# NeoCoreShield2.net
KiCad netlist of a schematic drawn in EAGLE
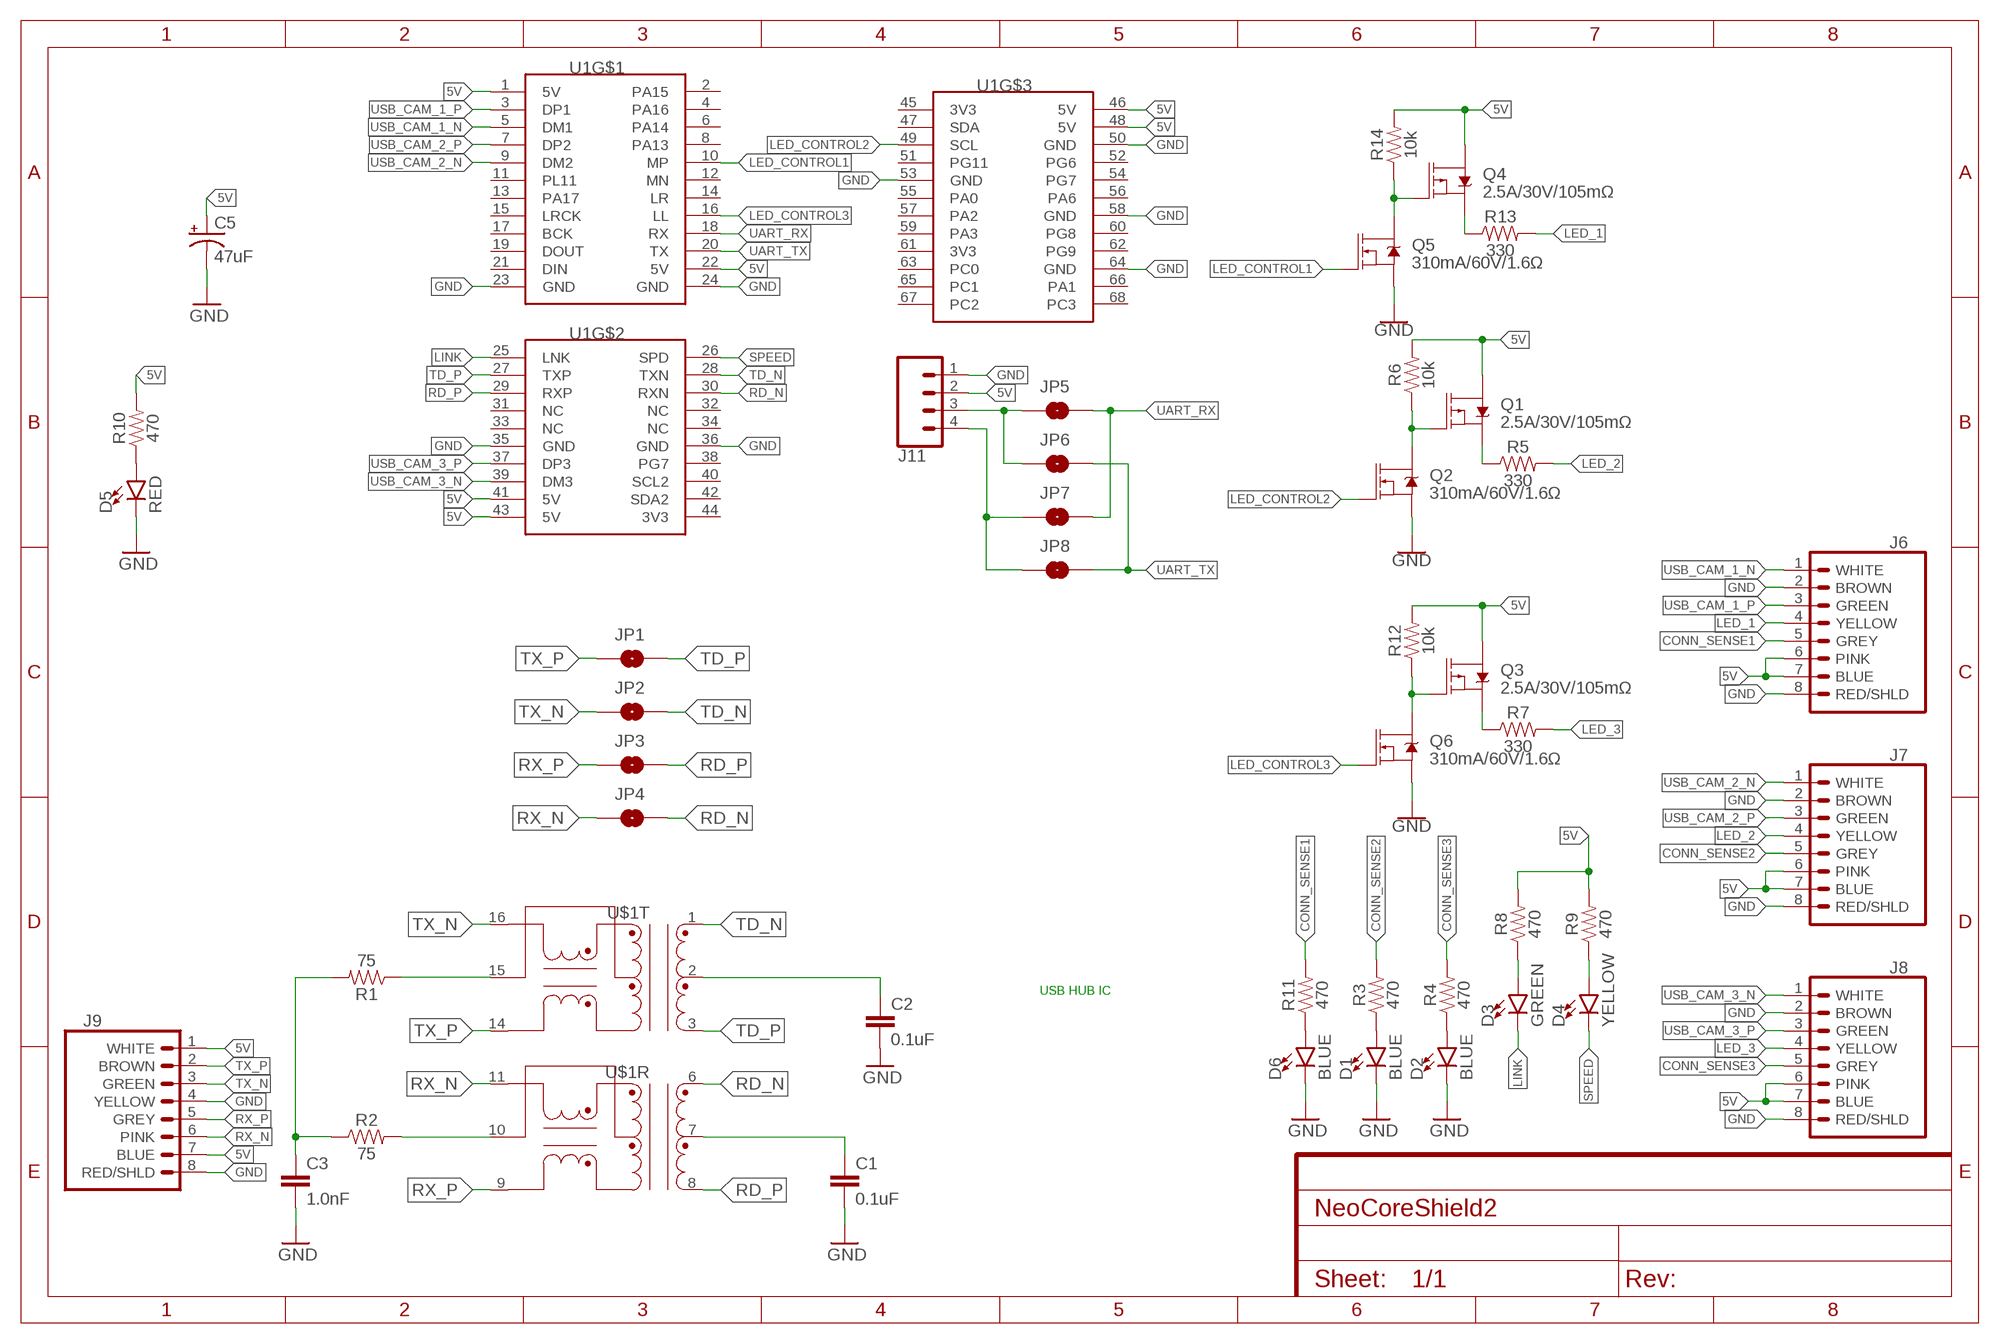
[diagram p0: schematic, sheet 1]

(export (version "E")
  (design (tool "Eeschema 10.0.6"))
  (components
    (comp (ref "C1")
      (value "0.1uF")
      (footprint "eagle-import:0603")
      (libsource (lib "eagle-import") (part "0.1UF-0603-25V-(+80/-20%)"))
    )
    (comp (ref "C2")
      (value "0.1uF")
      (footprint "eagle-import:0603")
      (libsource (lib "eagle-import") (part "0.1UF-0603-25V-(+80/-20%)"))
    )
    (comp (ref "C3")
      (value "1.0nF")
      (footprint "eagle-import:1206")
      (libsource (lib "eagle-import") (part "1.0UF-1206-50V-10%"))
    )
    (comp (ref "C5")
      (value "47uF")
      (footprint "eagle-import:PANASONIC_D")
      (libsource (lib "eagle-import") (part "47UF-POLAR-PANASONIC_D-35V-20%"))
    )
    (comp (ref "D1")
      (value "BLUE")
      (footprint "eagle-import:0805")
      (libsource (lib "eagle-import") (part "LED-0805"))
    )
    (comp (ref "D2")
      (value "BLUE")
      (footprint "eagle-import:0805")
      (libsource (lib "eagle-import") (part "LED-0805"))
    )
    (comp (ref "D3")
      (value "GREEN")
      (footprint "eagle-import:0805")
      (libsource (lib "eagle-import") (part "LED-0805"))
    )
    (comp (ref "D4")
      (value "YELLOW")
      (footprint "eagle-import:0805")
      (libsource (lib "eagle-import") (part "LED-0805"))
    )
    (comp (ref "D5")
      (value "RED")
      (footprint "eagle-import:0805")
      (libsource (lib "eagle-import") (part "LED-0805"))
    )
    (comp (ref "D6")
      (value "BLUE")
      (footprint "eagle-import:0805")
      (libsource (lib "eagle-import") (part "LED-0805"))
    )
    (comp (ref "J6")
      (value "BINDER_M12_PAR_8_DIP")
      (footprint "eagle-import:BINDER_M12_PAR_8_DIP")
      (libsource (lib "eagle-import") (part "BINDER_M12_PAR_8_DIP"))
    )
    (comp (ref "J7")
      (value "BINDER_M12_PAR_8_DIP")
      (footprint "eagle-import:BINDER_M12_PAR_8_DIP")
      (libsource (lib "eagle-import") (part "BINDER_M12_PAR_8_DIP"))
    )
    (comp (ref "J8")
      (value "BINDER_M12_PAR_8_DIP")
      (footprint "eagle-import:BINDER_M12_PAR_8_DIP")
      (libsource (lib "eagle-import") (part "BINDER_M12_PAR_8_DIP"))
    )
    (comp (ref "J9")
      (value "BINDER_M12_PAR_8_DIP")
      (footprint "eagle-import:BINDER_M12_PAR_8_DIP")
      (libsource (lib "eagle-import") (part "BINDER_M12_PAR_8_DIP"))
    )
    (comp (ref "J11")
      (value "CONN_04")
      (footprint "eagle-import:1X04")
      (libsource (lib "eagle-import") (part "CONN_04"))
    )
    (comp (ref "JP1")
      (value "JUMPER-SMT_2_NO_SILK")
      (footprint "eagle-import:SMT-JUMPER_2_NO_SILK")
      (libsource (lib "eagle-import") (part "JUMPER-SMT_2_NO_SILK"))
    )
    (comp (ref "JP2")
      (value "JUMPER-SMT_2_NO_SILK")
      (footprint "eagle-import:SMT-JUMPER_2_NO_SILK")
      (libsource (lib "eagle-import") (part "JUMPER-SMT_2_NO_SILK"))
    )
    (comp (ref "JP3")
      (value "JUMPER-SMT_2_NO_SILK")
      (footprint "eagle-import:SMT-JUMPER_2_NO_SILK")
      (libsource (lib "eagle-import") (part "JUMPER-SMT_2_NO_SILK"))
    )
    (comp (ref "JP4")
      (value "JUMPER-SMT_2_NO_SILK")
      (footprint "eagle-import:SMT-JUMPER_2_NO_SILK")
      (libsource (lib "eagle-import") (part "JUMPER-SMT_2_NO_SILK"))
    )
    (comp (ref "JP5")
      (value "JUMPER-SMT_2_NO_SILK")
      (footprint "eagle-import:SMT-JUMPER_2_NO_SILK")
      (libsource (lib "eagle-import") (part "JUMPER-SMT_2_NO_SILK"))
    )
    (comp (ref "JP6")
      (value "JUMPER-SMT_2_NO_SILK")
      (footprint "eagle-import:SMT-JUMPER_2_NO_SILK")
      (libsource (lib "eagle-import") (part "JUMPER-SMT_2_NO_SILK"))
    )
    (comp (ref "JP7")
      (value "JUMPER-SMT_2_NO_SILK")
      (footprint "eagle-import:SMT-JUMPER_2_NO_SILK")
      (libsource (lib "eagle-import") (part "JUMPER-SMT_2_NO_SILK"))
    )
    (comp (ref "JP8")
      (value "JUMPER-SMT_2_NO_SILK")
      (footprint "eagle-import:SMT-JUMPER_2_NO_SILK")
      (libsource (lib "eagle-import") (part "JUMPER-SMT_2_NO_SILK"))
    )
    (comp (ref "Q1")
      (value "2.5A/30V/105mΩ")
      (footprint "eagle-import:SOT23-3")
      (libsource (lib "eagle-import") (part "MOSFET_PCH-DMG2307L"))
    )
    (comp (ref "Q2")
      (value "310mA/60V/1.6Ω")
      (footprint "eagle-import:SOT323")
      (libsource (lib "eagle-import") (part "MOSFET-NCH-2N7002PW"))
    )
    (comp (ref "Q3")
      (value "2.5A/30V/105mΩ")
      (footprint "eagle-import:SOT23-3")
      (libsource (lib "eagle-import") (part "MOSFET_PCH-DMG2307L"))
    )
    (comp (ref "Q4")
      (value "2.5A/30V/105mΩ")
      (footprint "eagle-import:SOT23-3")
      (libsource (lib "eagle-import") (part "MOSFET_PCH-DMG2307L"))
    )
    (comp (ref "Q5")
      (value "310mA/60V/1.6Ω")
      (footprint "eagle-import:SOT323")
      (libsource (lib "eagle-import") (part "MOSFET-NCH-2N7002PW"))
    )
    (comp (ref "Q6")
      (value "310mA/60V/1.6Ω")
      (footprint "eagle-import:SOT323")
      (libsource (lib "eagle-import") (part "MOSFET-NCH-2N7002PW"))
    )
    (comp (ref "R1")
      (value "75")
      (footprint "eagle-import:0603")
      (libsource (lib "eagle-import") (part "75KOHM-0603-1/10W-1%"))
    )
    (comp (ref "R2")
      (value "75")
      (footprint "eagle-import:0603")
      (libsource (lib "eagle-import") (part "75KOHM-0603-1/10W-1%"))
    )
    (comp (ref "R3")
      (value "470")
      (footprint "eagle-import:0603")
      (libsource (lib "eagle-import") (part "0OHM-0603-1/10W-5%"))
    )
    (comp (ref "R4")
      (value "470")
      (footprint "eagle-import:0603")
      (libsource (lib "eagle-import") (part "0OHM-0603-1/10W-5%"))
    )
    (comp (ref "R5")
      (value "330")
      (footprint "eagle-import:0805")
      (libsource (lib "eagle-import") (part "RESISTOR0805"))
    )
    (comp (ref "R6")
      (value "10k")
      (footprint "eagle-import:0603")
      (libsource (lib "eagle-import") (part "10KOHM-0603-1/10W-1%"))
    )
    (comp (ref "R7")
      (value "330")
      (footprint "eagle-import:0805")
      (libsource (lib "eagle-import") (part "RESISTOR0805"))
    )
    (comp (ref "R8")
      (value "470")
      (footprint "eagle-import:0603")
      (libsource (lib "eagle-import") (part "0OHM-0603-1/10W-5%"))
    )
    (comp (ref "R9")
      (value "470")
      (footprint "eagle-import:0603")
      (libsource (lib "eagle-import") (part "0OHM-0603-1/10W-5%"))
    )
    (comp (ref "R10")
      (value "470")
      (footprint "eagle-import:0603")
      (libsource (lib "eagle-import") (part "0OHM-0603-1/10W-5%"))
    )
    (comp (ref "R11")
      (value "470")
      (footprint "eagle-import:0603")
      (libsource (lib "eagle-import") (part "0OHM-0603-1/10W-5%"))
    )
    (comp (ref "R12")
      (value "10k")
      (footprint "eagle-import:0603")
      (libsource (lib "eagle-import") (part "10KOHM-0603-1/10W-1%"))
    )
    (comp (ref "R13")
      (value "330")
      (footprint "eagle-import:0805")
      (libsource (lib "eagle-import") (part "RESISTOR0805"))
    )
    (comp (ref "R14")
      (value "10k")
      (footprint "eagle-import:0603")
      (libsource (lib "eagle-import") (part "10KOHM-0603-1/10W-1%"))
    )
    (comp (ref "U$1")
      (value "ETH-TRANS")
      (footprint "eagle-import:SOIC-16-WIDE")
      (libsource (lib "eagle-import") (part "ETH-TRANS"))
    )
    (comp (ref "U1")
      (value "NANO_PI_NEO_CORE")
      (footprint "eagle-import:NANO_PI_NEO_CORE")
      (libsource (lib "eagle-import") (part "NANO_PI_NEO_CORE"))
    )
  )
  (nets
    (net (code "1") (name "5V") (class "Default")
      (node (ref "C5") (pin "+") (pinfunction "+_+") (pintype "passive"))
      (node (ref "J11") (pin "2") (pinfunction "2_2") (pintype "passive"))
      (node (ref "J6") (pin "6") (pinfunction "PINK_6") (pintype "passive"))
      (node (ref "J6") (pin "7") (pinfunction "BLUE_7") (pintype "passive"))
      (node (ref "J7") (pin "6") (pinfunction "PINK_6") (pintype "passive"))
      (node (ref "J7") (pin "7") (pinfunction "BLUE_7") (pintype "passive"))
      (node (ref "J8") (pin "6") (pinfunction "PINK_6") (pintype "passive"))
      (node (ref "J8") (pin "7") (pinfunction "BLUE_7") (pintype "passive"))
      (node (ref "J9") (pin "1") (pinfunction "WHITE_1") (pintype "passive"))
      (node (ref "J9") (pin "7") (pinfunction "BLUE_7") (pintype "passive"))
      (node (ref "Q1") (pin "3") (pinfunction "D_3") (pintype "bidirectional"))
      (node (ref "Q3") (pin "3") (pinfunction "D_3") (pintype "bidirectional"))
      (node (ref "Q4") (pin "3") (pinfunction "D_3") (pintype "bidirectional"))
      (node (ref "R10") (pin "2") (pinfunction "2_2") (pintype "passive"))
      (node (ref "R12") (pin "2") (pinfunction "2_2") (pintype "passive"))
      (node (ref "R14") (pin "2") (pinfunction "2_2") (pintype "passive"))
      (node (ref "R6") (pin "2") (pinfunction "2_2") (pintype "passive"))
      (node (ref "R8") (pin "2") (pinfunction "2_2") (pintype "passive"))
      (node (ref "R9") (pin "2") (pinfunction "2_2") (pintype "passive"))
      (node (ref "U1") (pin "1") (pinfunction "5V_1") (pintype "bidirectional"))
      (node (ref "U1") (pin "22") (pinfunction "5V_22") (pintype "bidirectional"))
      (node (ref "U1") (pin "41") (pinfunction "5V_41") (pintype "bidirectional"))
      (node (ref "U1") (pin "43") (pinfunction "5V_43") (pintype "bidirectional"))
      (node (ref "U1") (pin "46") (pinfunction "5V_46") (pintype "bidirectional"))
      (node (ref "U1") (pin "48") (pinfunction "5V_48") (pintype "bidirectional"))
    )
    (net (code "2") (name "CONN_SENSE1") (class "Default")
      (node (ref "J6") (pin "5") (pinfunction "GREY_5") (pintype "passive"))
      (node (ref "R11") (pin "2") (pinfunction "2_2") (pintype "passive"))
    )
    (net (code "3") (name "CONN_SENSE2") (class "Default")
      (node (ref "J7") (pin "5") (pinfunction "GREY_5") (pintype "passive"))
      (node (ref "R3") (pin "2") (pinfunction "2_2") (pintype "passive"))
    )
    (net (code "4") (name "CONN_SENSE3") (class "Default")
      (node (ref "J8") (pin "5") (pinfunction "GREY_5") (pintype "passive"))
      (node (ref "R4") (pin "2") (pinfunction "2_2") (pintype "passive"))
    )
    (net (code "5") (name "GND") (class "Default")
      (node (ref "C1") (pin "2") (pinfunction "2_2") (pintype "passive"))
      (node (ref "C2") (pin "2") (pinfunction "2_2") (pintype "passive"))
      (node (ref "C3") (pin "2") (pinfunction "2_2") (pintype "passive"))
      (node (ref "C5") (pin "-") (pinfunction "-_-") (pintype "passive"))
      (node (ref "D1") (pin "C") (pinfunction "C_C") (pintype "passive"))
      (node (ref "D2") (pin "C") (pinfunction "C_C") (pintype "passive"))
      (node (ref "D5") (pin "C") (pinfunction "C_C") (pintype "passive"))
      (node (ref "D6") (pin "C") (pinfunction "C_C") (pintype "passive"))
      (node (ref "J11") (pin "1") (pinfunction "1_1") (pintype "passive"))
      (node (ref "J6") (pin "2") (pinfunction "BROWN_2") (pintype "passive"))
      (node (ref "J6") (pin "8") (pinfunction "RED/SHLD_8") (pintype "passive"))
      (node (ref "J7") (pin "2") (pinfunction "BROWN_2") (pintype "passive"))
      (node (ref "J7") (pin "8") (pinfunction "RED/SHLD_8") (pintype "passive"))
      (node (ref "J8") (pin "2") (pinfunction "BROWN_2") (pintype "passive"))
      (node (ref "J8") (pin "8") (pinfunction "RED/SHLD_8") (pintype "passive"))
      (node (ref "J9") (pin "4") (pinfunction "YELLOW_4") (pintype "passive"))
      (node (ref "J9") (pin "8") (pinfunction "RED/SHLD_8") (pintype "passive"))
      (node (ref "Q2") (pin "2") (pinfunction "S_2") (pintype "bidirectional"))
      (node (ref "Q5") (pin "2") (pinfunction "S_2") (pintype "bidirectional"))
      (node (ref "Q6") (pin "2") (pinfunction "S_2") (pintype "bidirectional"))
      (node (ref "U1") (pin "23") (pinfunction "GND_23") (pintype "bidirectional"))
      (node (ref "U1") (pin "24") (pinfunction "GND_24") (pintype "bidirectional"))
      (node (ref "U1") (pin "35") (pinfunction "GND_35") (pintype "bidirectional"))
      (node (ref "U1") (pin "36") (pinfunction "GND_36") (pintype "bidirectional"))
      (node (ref "U1") (pin "50") (pinfunction "GND_50") (pintype "bidirectional"))
      (node (ref "U1") (pin "53") (pinfunction "GND_53") (pintype "bidirectional"))
      (node (ref "U1") (pin "58") (pinfunction "GND_58") (pintype "bidirectional"))
      (node (ref "U1") (pin "64") (pinfunction "GND_64") (pintype "bidirectional"))
    )
    (net (code "6") (name "LED_1") (class "Default")
      (node (ref "J6") (pin "4") (pinfunction "YELLOW_4") (pintype "passive"))
      (node (ref "R13") (pin "2") (pinfunction "2_2") (pintype "passive"))
    )
    (net (code "7") (name "LED_2") (class "Default")
      (node (ref "J7") (pin "4") (pinfunction "YELLOW_4") (pintype "passive"))
      (node (ref "R5") (pin "2") (pinfunction "2_2") (pintype "passive"))
    )
    (net (code "8") (name "LED_3") (class "Default")
      (node (ref "J8") (pin "4") (pinfunction "YELLOW_4") (pintype "passive"))
      (node (ref "R7") (pin "2") (pinfunction "2_2") (pintype "passive"))
    )
    (net (code "9") (name "LED_CONTROL1") (class "Default")
      (node (ref "Q5") (pin "1") (pinfunction "G_1") (pintype "bidirectional"))
      (node (ref "U1") (pin "10") (pinfunction "MP_10") (pintype "bidirectional"))
    )
    (net (code "10") (name "LED_CONTROL2") (class "Default")
      (node (ref "Q2") (pin "1") (pinfunction "G_1") (pintype "bidirectional"))
      (node (ref "U1") (pin "49") (pinfunction "SCL_49") (pintype "bidirectional"))
    )
    (net (code "11") (name "LED_CONTROL3") (class "Default")
      (node (ref "Q6") (pin "1") (pinfunction "G_1") (pintype "bidirectional"))
      (node (ref "U1") (pin "16") (pinfunction "LL_16") (pintype "bidirectional"))
    )
    (net (code "12") (name "LINK") (class "Default")
      (node (ref "D3") (pin "C") (pinfunction "C_C") (pintype "passive"))
      (node (ref "U1") (pin "25") (pinfunction "LNK_25") (pintype "bidirectional"))
    )
    (net (code "13") (name "Net-(C3-Pad1)") (class "Default")
      (node (ref "C3") (pin "1") (pinfunction "1_1") (pintype "passive"))
      (node (ref "R1") (pin "2") (pinfunction "2_2") (pintype "passive"))
      (node (ref "R2") (pin "1") (pinfunction "1_1") (pintype "passive"))
    )
    (net (code "14") (name "Net-(D1-PadA)") (class "Default")
      (node (ref "D1") (pin "A") (pinfunction "A_A") (pintype "passive"))
      (node (ref "R3") (pin "1") (pinfunction "1_1") (pintype "passive"))
    )
    (net (code "15") (name "Net-(D2-PadA)") (class "Default")
      (node (ref "D2") (pin "A") (pinfunction "A_A") (pintype "passive"))
      (node (ref "R4") (pin "1") (pinfunction "1_1") (pintype "passive"))
    )
    (net (code "16") (name "Net-(D3-PadA)") (class "Default")
      (node (ref "D3") (pin "A") (pinfunction "A_A") (pintype "passive"))
      (node (ref "R8") (pin "1") (pinfunction "1_1") (pintype "passive"))
    )
    (net (code "17") (name "Net-(D4-PadA)") (class "Default")
      (node (ref "D4") (pin "A") (pinfunction "A_A") (pintype "passive"))
      (node (ref "R9") (pin "1") (pinfunction "1_1") (pintype "passive"))
    )
    (net (code "18") (name "Net-(D5-PadA)") (class "Default")
      (node (ref "D5") (pin "A") (pinfunction "A_A") (pintype "passive"))
      (node (ref "R10") (pin "1") (pinfunction "1_1") (pintype "passive"))
    )
    (net (code "19") (name "Net-(D6-PadA)") (class "Default")
      (node (ref "D6") (pin "A") (pinfunction "A_A") (pintype "passive"))
      (node (ref "R11") (pin "1") (pinfunction "1_1") (pintype "passive"))
    )
    (net (code "20") (name "Net-(J11-Pad3)") (class "Default")
      (node (ref "J11") (pin "3") (pinfunction "3_3") (pintype "passive"))
      (node (ref "JP5") (pin "1") (pinfunction "1_1") (pintype "passive"))
      (node (ref "JP6") (pin "1") (pinfunction "1_1") (pintype "passive"))
    )
    (net (code "21") (name "Net-(J11-Pad4)") (class "Default")
      (node (ref "J11") (pin "4") (pinfunction "4_4") (pintype "passive"))
      (node (ref "JP7") (pin "1") (pinfunction "1_1") (pintype "passive"))
      (node (ref "JP8") (pin "1") (pinfunction "1_1") (pintype "passive"))
    )
    (net (code "22") (name "Net-(Q1-G)") (class "Default")
      (node (ref "Q1") (pin "1") (pinfunction "G_1") (pintype "bidirectional"))
      (node (ref "Q2") (pin "3") (pinfunction "D_3") (pintype "bidirectional"))
      (node (ref "R6") (pin "1") (pinfunction "1_1") (pintype "passive"))
    )
    (net (code "23") (name "Net-(Q1-S)") (class "Default")
      (node (ref "Q1") (pin "2") (pinfunction "S_2") (pintype "bidirectional"))
      (node (ref "R5") (pin "1") (pinfunction "1_1") (pintype "passive"))
    )
    (net (code "24") (name "Net-(Q3-G)") (class "Default")
      (node (ref "Q3") (pin "1") (pinfunction "G_1") (pintype "bidirectional"))
      (node (ref "Q6") (pin "3") (pinfunction "D_3") (pintype "bidirectional"))
      (node (ref "R12") (pin "1") (pinfunction "1_1") (pintype "passive"))
    )
    (net (code "25") (name "Net-(Q3-S)") (class "Default")
      (node (ref "Q3") (pin "2") (pinfunction "S_2") (pintype "bidirectional"))
      (node (ref "R7") (pin "1") (pinfunction "1_1") (pintype "passive"))
    )
    (net (code "26") (name "Net-(Q4-G)") (class "Default")
      (node (ref "Q4") (pin "1") (pinfunction "G_1") (pintype "bidirectional"))
      (node (ref "Q5") (pin "3") (pinfunction "D_3") (pintype "bidirectional"))
      (node (ref "R14") (pin "1") (pinfunction "1_1") (pintype "passive"))
    )
    (net (code "27") (name "Net-(Q4-S)") (class "Default")
      (node (ref "Q4") (pin "2") (pinfunction "S_2") (pintype "bidirectional"))
      (node (ref "R13") (pin "1") (pinfunction "1_1") (pintype "passive"))
    )
    (net (code "28") (name "Net-(U$1A-CT)") (class "Default")
      (node (ref "C1") (pin "1") (pinfunction "1_1") (pintype "passive"))
      (node (ref "U$1") (pin "7") (pinfunction "CT_7") (pintype "passive"))
    )
    (net (code "29") (name "Net-(U$1A-XCT)") (class "Default")
      (node (ref "R2") (pin "2") (pinfunction "2_2") (pintype "passive"))
      (node (ref "U$1") (pin "10") (pinfunction "XCT_10") (pintype "passive"))
    )
    (net (code "30") (name "Net-(U$1B-CT)") (class "Default")
      (node (ref "C2") (pin "1") (pinfunction "1_1") (pintype "passive"))
      (node (ref "U$1") (pin "2") (pinfunction "CT_2") (pintype "passive"))
    )
    (net (code "31") (name "Net-(U$1B-XCT)") (class "Default")
      (node (ref "R1") (pin "1") (pinfunction "1_1") (pintype "passive"))
      (node (ref "U$1") (pin "15") (pinfunction "XCT_15") (pintype "passive"))
    )
    (net (code "32") (name "RD_N") (class "Default")
      (node (ref "JP4") (pin "2") (pinfunction "2_2") (pintype "passive"))
      (node (ref "U$1") (pin "6") (pinfunction "D+_6") (pintype "passive"))
      (node (ref "U1") (pin "30") (pinfunction "RXN_30") (pintype "bidirectional"))
    )
    (net (code "33") (name "RD_P") (class "Default")
      (node (ref "JP3") (pin "2") (pinfunction "2_2") (pintype "passive"))
      (node (ref "U$1") (pin "8") (pinfunction "D-_8") (pintype "passive"))
      (node (ref "U1") (pin "29") (pinfunction "RXP_29") (pintype "bidirectional"))
    )
    (net (code "34") (name "RX_N") (class "Default")
      (node (ref "J9") (pin "6") (pinfunction "PINK_6") (pintype "passive"))
      (node (ref "JP4") (pin "1") (pinfunction "1_1") (pintype "passive"))
      (node (ref "U$1") (pin "11") (pinfunction "X+_11") (pintype "passive"))
    )
    (net (code "35") (name "RX_P") (class "Default")
      (node (ref "J9") (pin "5") (pinfunction "GREY_5") (pintype "passive"))
      (node (ref "JP3") (pin "1") (pinfunction "1_1") (pintype "passive"))
      (node (ref "U$1") (pin "9") (pinfunction "X-_9") (pintype "passive"))
    )
    (net (code "36") (name "SPEED") (class "Default")
      (node (ref "D4") (pin "C") (pinfunction "C_C") (pintype "passive"))
      (node (ref "U1") (pin "26") (pinfunction "SPD_26") (pintype "bidirectional"))
    )
    (net (code "37") (name "TD_N") (class "Default")
      (node (ref "JP2") (pin "2") (pinfunction "2_2") (pintype "passive"))
      (node (ref "U$1") (pin "1") (pinfunction "D+_1") (pintype "passive"))
      (node (ref "U1") (pin "28") (pinfunction "TXN_28") (pintype "bidirectional"))
    )
    (net (code "38") (name "TD_P") (class "Default")
      (node (ref "JP1") (pin "2") (pinfunction "2_2") (pintype "passive"))
      (node (ref "U$1") (pin "3") (pinfunction "D-_3") (pintype "passive"))
      (node (ref "U1") (pin "27") (pinfunction "TXP_27") (pintype "bidirectional"))
    )
    (net (code "39") (name "TX_N") (class "Default")
      (node (ref "J9") (pin "3") (pinfunction "GREEN_3") (pintype "passive"))
      (node (ref "JP2") (pin "1") (pinfunction "1_1") (pintype "passive"))
      (node (ref "U$1") (pin "16") (pinfunction "X+_16") (pintype "passive"))
    )
    (net (code "40") (name "TX_P") (class "Default")
      (node (ref "J9") (pin "2") (pinfunction "BROWN_2") (pintype "passive"))
      (node (ref "JP1") (pin "1") (pinfunction "1_1") (pintype "passive"))
      (node (ref "U$1") (pin "14") (pinfunction "X-_14") (pintype "passive"))
    )
    (net (code "41") (name "UART_RX") (class "Default")
      (node (ref "JP5") (pin "2") (pinfunction "2_2") (pintype "passive"))
      (node (ref "JP7") (pin "2") (pinfunction "2_2") (pintype "passive"))
      (node (ref "U1") (pin "18") (pinfunction "RX_18") (pintype "bidirectional"))
    )
    (net (code "42") (name "UART_TX") (class "Default")
      (node (ref "JP6") (pin "2") (pinfunction "2_2") (pintype "passive"))
      (node (ref "JP8") (pin "2") (pinfunction "2_2") (pintype "passive"))
      (node (ref "U1") (pin "20") (pinfunction "TX_20") (pintype "bidirectional"))
    )
    (net (code "43") (name "USB_CAM_1_N") (class "Default")
      (node (ref "J6") (pin "1") (pinfunction "WHITE_1") (pintype "passive"))
      (node (ref "U1") (pin "5") (pinfunction "DM1_5") (pintype "bidirectional"))
    )
    (net (code "44") (name "USB_CAM_1_P") (class "Default")
      (node (ref "J6") (pin "3") (pinfunction "GREEN_3") (pintype "passive"))
      (node (ref "U1") (pin "3") (pinfunction "DP1_3") (pintype "bidirectional"))
    )
    (net (code "45") (name "USB_CAM_2_N") (class "Default")
      (node (ref "J7") (pin "1") (pinfunction "WHITE_1") (pintype "passive"))
      (node (ref "U1") (pin "9") (pinfunction "DM2_9") (pintype "bidirectional"))
    )
    (net (code "46") (name "USB_CAM_2_P") (class "Default")
      (node (ref "J7") (pin "3") (pinfunction "GREEN_3") (pintype "passive"))
      (node (ref "U1") (pin "7") (pinfunction "DP2_7") (pintype "bidirectional"))
    )
    (net (code "47") (name "USB_CAM_3_N") (class "Default")
      (node (ref "J8") (pin "1") (pinfunction "WHITE_1") (pintype "passive"))
      (node (ref "U1") (pin "39") (pinfunction "DM3_39") (pintype "bidirectional"))
    )
    (net (code "48") (name "USB_CAM_3_P") (class "Default")
      (node (ref "J8") (pin "3") (pinfunction "GREEN_3") (pintype "passive"))
      (node (ref "U1") (pin "37") (pinfunction "DP3_37") (pintype "bidirectional"))
    )
    (net (code "49") (name "unconnected-(U1A-BCK-Pad17)") (class "Default")
      (node (ref "U1") (pin "17") (pinfunction "BCK_17") (pintype "bidirectional"))
    )
    (net (code "50") (name "unconnected-(U1A-DIN-Pad21)") (class "Default")
      (node (ref "U1") (pin "21") (pinfunction "DIN_21") (pintype "bidirectional"))
    )
    (net (code "51") (name "unconnected-(U1A-DOUT-Pad19)") (class "Default")
      (node (ref "U1") (pin "19") (pinfunction "DOUT_19") (pintype "bidirectional"))
    )
    (net (code "52") (name "unconnected-(U1A-LR-Pad14)") (class "Default")
      (node (ref "U1") (pin "14") (pinfunction "LR_14") (pintype "bidirectional"))
    )
    (net (code "53") (name "unconnected-(U1A-LRCK-Pad15)") (class "Default")
      (node (ref "U1") (pin "15") (pinfunction "LRCK_15") (pintype "bidirectional"))
    )
    (net (code "54") (name "unconnected-(U1A-MN-Pad12)") (class "Default")
      (node (ref "U1") (pin "12") (pinfunction "MN_12") (pintype "bidirectional"))
    )
    (net (code "55") (name "unconnected-(U1A-PA13-Pad8)") (class "Default")
      (node (ref "U1") (pin "8") (pinfunction "PA13_8") (pintype "bidirectional"))
    )
    (net (code "56") (name "unconnected-(U1A-PA14-Pad6)") (class "Default")
      (node (ref "U1") (pin "6") (pinfunction "PA14_6") (pintype "bidirectional"))
    )
    (net (code "57") (name "unconnected-(U1A-PA15-Pad2)") (class "Default")
      (node (ref "U1") (pin "2") (pinfunction "PA15_2") (pintype "bidirectional"))
    )
    (net (code "58") (name "unconnected-(U1A-PA16-Pad4)") (class "Default")
      (node (ref "U1") (pin "4") (pinfunction "PA16_4") (pintype "bidirectional"))
    )
    (net (code "59") (name "unconnected-(U1A-PA17-Pad13)") (class "Default")
      (node (ref "U1") (pin "13") (pinfunction "PA17_13") (pintype "bidirectional"))
    )
    (net (code "60") (name "unconnected-(U1A-PL11-Pad11)") (class "Default")
      (node (ref "U1") (pin "11") (pinfunction "PL11_11") (pintype "bidirectional"))
    )
    (net (code "61") (name "unconnected-(U1B-3V3-Pad44)") (class "Default")
      (node (ref "U1") (pin "44") (pinfunction "3V3_44") (pintype "bidirectional"))
    )
    (net (code "62") (name "unconnected-(U1B-NC-Pad31)") (class "Default")
      (node (ref "U1") (pin "31") (pinfunction "NC_31") (pintype "bidirectional"))
    )
    (net (code "63") (name "unconnected-(U1B-NC-Pad32)") (class "Default")
      (node (ref "U1") (pin "32") (pinfunction "NC_32") (pintype "bidirectional"))
    )
    (net (code "64") (name "unconnected-(U1B-NC-Pad33)") (class "Default")
      (node (ref "U1") (pin "33") (pinfunction "NC_33") (pintype "bidirectional"))
    )
    (net (code "65") (name "unconnected-(U1B-NC-Pad34)") (class "Default")
      (node (ref "U1") (pin "34") (pinfunction "NC_34") (pintype "bidirectional"))
    )
    (net (code "66") (name "unconnected-(U1B-PG7-Pad38)") (class "Default")
      (node (ref "U1") (pin "38") (pinfunction "PG7_38") (pintype "bidirectional"))
    )
    (net (code "67") (name "unconnected-(U1B-SCL2-Pad40)") (class "Default")
      (node (ref "U1") (pin "40") (pinfunction "SCL2_40") (pintype "bidirectional"))
    )
    (net (code "68") (name "unconnected-(U1B-SDA2-Pad42)") (class "Default")
      (node (ref "U1") (pin "42") (pinfunction "SDA2_42") (pintype "bidirectional"))
    )
    (net (code "69") (name "unconnected-(U1C-3V3-Pad45)") (class "Default")
      (node (ref "U1") (pin "45") (pinfunction "3V3_45") (pintype "bidirectional"))
    )
    (net (code "70") (name "unconnected-(U1C-3V3-Pad61)") (class "Default")
      (node (ref "U1") (pin "61") (pinfunction "3V3_61") (pintype "bidirectional"))
    )
    (net (code "71") (name "unconnected-(U1C-PA0-Pad55)") (class "Default")
      (node (ref "U1") (pin "55") (pinfunction "PA0_55") (pintype "bidirectional"))
    )
    (net (code "72") (name "unconnected-(U1C-PA1-Pad66)") (class "Default")
      (node (ref "U1") (pin "66") (pinfunction "PA1_66") (pintype "bidirectional"))
    )
    (net (code "73") (name "unconnected-(U1C-PA2-Pad57)") (class "Default")
      (node (ref "U1") (pin "57") (pinfunction "PA2_57") (pintype "bidirectional"))
    )
    (net (code "74") (name "unconnected-(U1C-PA3-Pad59)") (class "Default")
      (node (ref "U1") (pin "59") (pinfunction "PA3_59") (pintype "bidirectional"))
    )
    (net (code "75") (name "unconnected-(U1C-PA6-Pad56)") (class "Default")
      (node (ref "U1") (pin "56") (pinfunction "PA6_56") (pintype "bidirectional"))
    )
    (net (code "76") (name "unconnected-(U1C-PC0-Pad63)") (class "Default")
      (node (ref "U1") (pin "63") (pinfunction "PC0_63") (pintype "bidirectional"))
    )
    (net (code "77") (name "unconnected-(U1C-PC1-Pad65)") (class "Default")
      (node (ref "U1") (pin "65") (pinfunction "PC1_65") (pintype "bidirectional"))
    )
    (net (code "78") (name "unconnected-(U1C-PC2-Pad67)") (class "Default")
      (node (ref "U1") (pin "67") (pinfunction "PC2_67") (pintype "bidirectional"))
    )
    (net (code "79") (name "unconnected-(U1C-PC3-Pad68)") (class "Default")
      (node (ref "U1") (pin "68") (pinfunction "PC3_68") (pintype "bidirectional"))
    )
    (net (code "80") (name "unconnected-(U1C-PG6-Pad52)") (class "Default")
      (node (ref "U1") (pin "52") (pinfunction "PG6_52") (pintype "bidirectional"))
    )
    (net (code "81") (name "unconnected-(U1C-PG7-Pad54)") (class "Default")
      (node (ref "U1") (pin "54") (pinfunction "PG7_54") (pintype "bidirectional"))
    )
    (net (code "82") (name "unconnected-(U1C-PG8-Pad60)") (class "Default")
      (node (ref "U1") (pin "60") (pinfunction "PG8_60") (pintype "bidirectional"))
    )
    (net (code "83") (name "unconnected-(U1C-PG9-Pad62)") (class "Default")
      (node (ref "U1") (pin "62") (pinfunction "PG9_62") (pintype "bidirectional"))
    )
    (net (code "84") (name "unconnected-(U1C-PG11-Pad51)") (class "Default")
      (node (ref "U1") (pin "51") (pinfunction "PG11_51") (pintype "bidirectional"))
    )
    (net (code "85") (name "unconnected-(U1C-SDA-Pad47)") (class "Default")
      (node (ref "U1") (pin "47") (pinfunction "SDA_47") (pintype "bidirectional"))
    )
  )
)
